# Arduino_sensors.net
KiCad netlist of a schematic drawn in EAGLE
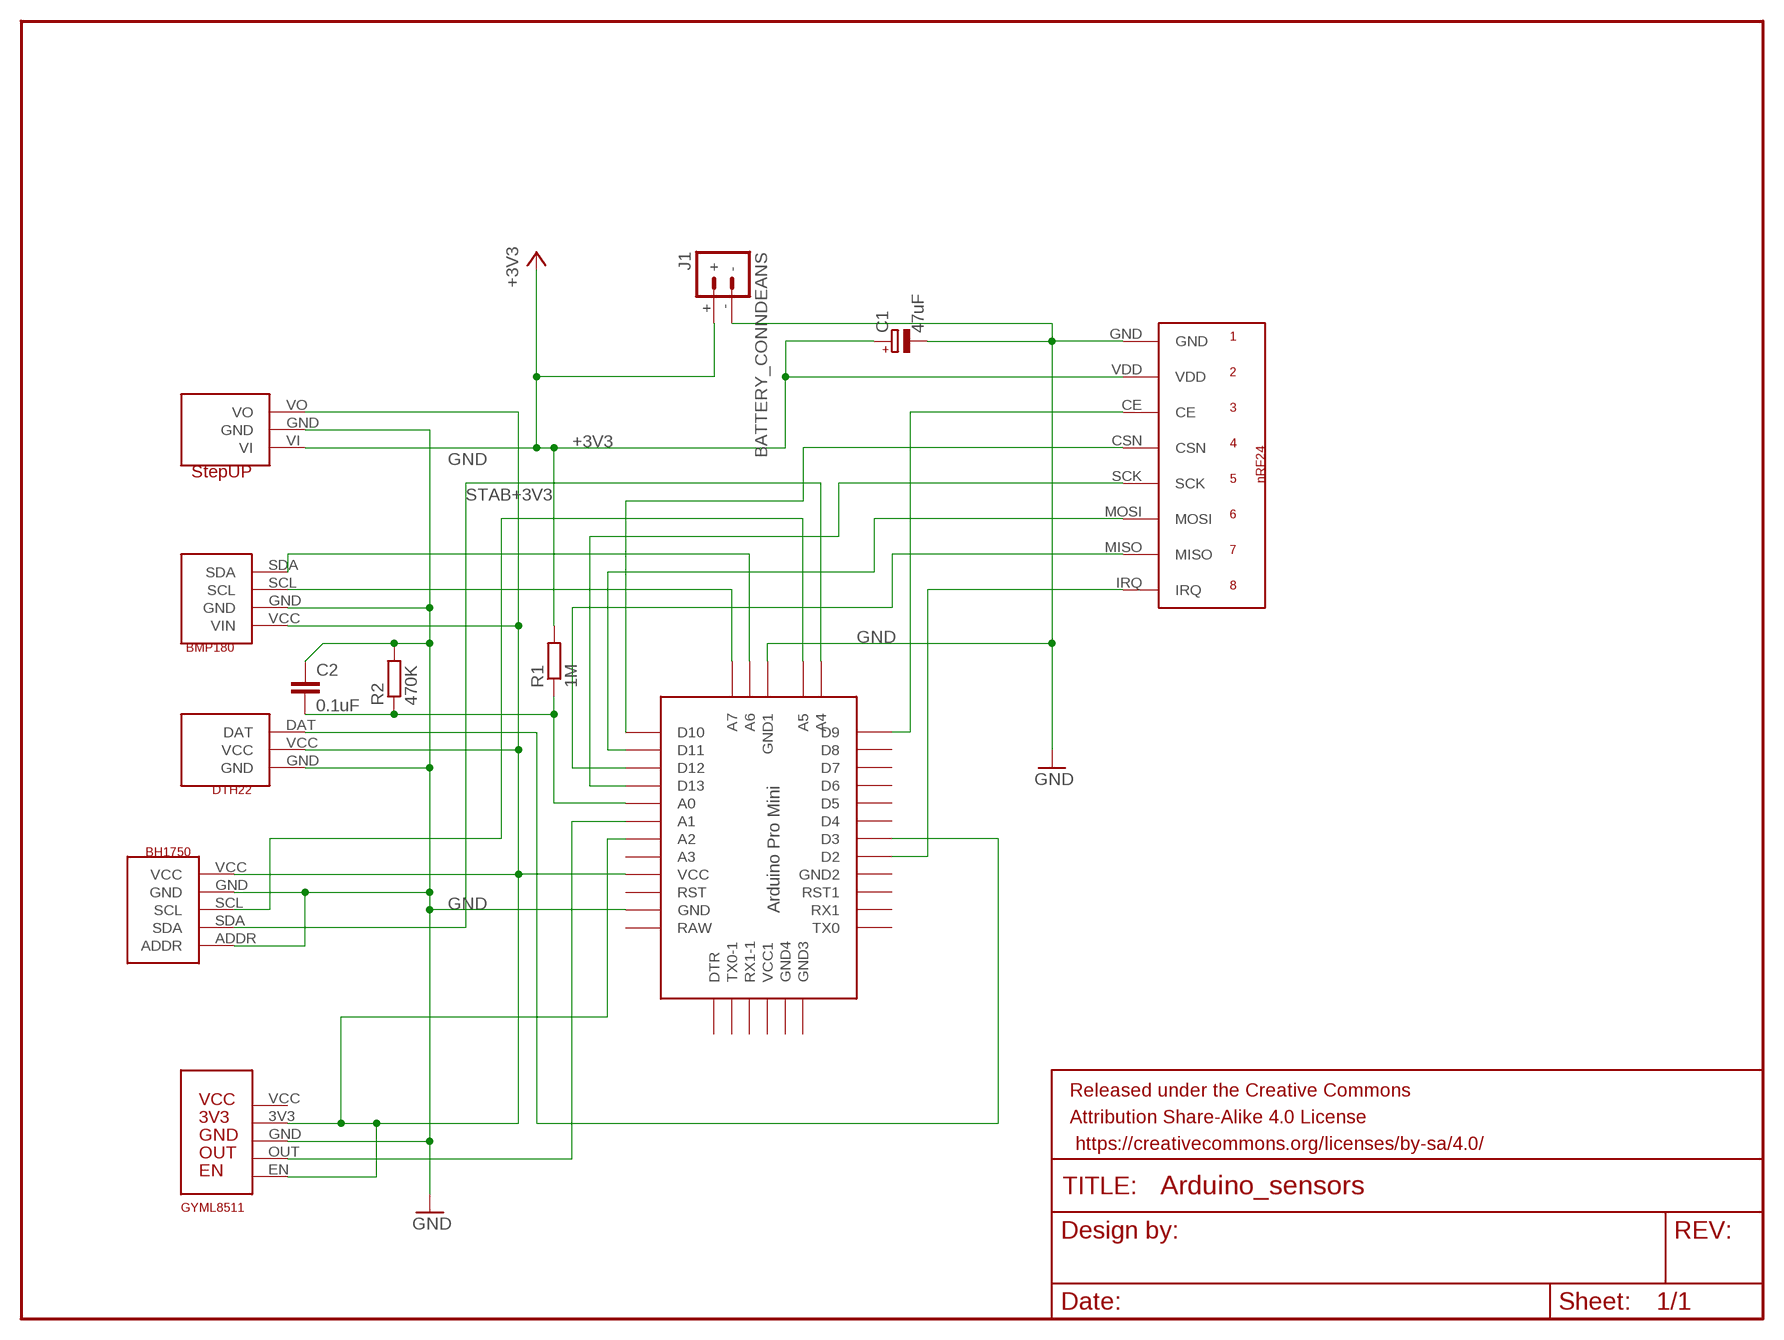
[diagram p0: schematic, sheet 1]

(export (version "E")
  (design (tool "Eeschema 10.0.6"))
  (components
    (comp (ref "ARDUINO_MINI")
      (value "ABK-PRO-MINI")
      (footprint "eagle-import:ABK-PRO-MINI")
      (libsource (lib "eagle-import") (part "ABK-PRO-MINI"))
    )
    (comp (ref "BH1")
      (value "BH1750")
      (footprint "eagle-import:BH1750")
      (libsource (lib "eagle-import") (part "BH1750"))
    )
    (comp (ref "BMP1")
      (value "BMP180")
      (footprint "eagle-import:BMP180")
      (libsource (lib "eagle-import") (part "BMP180"))
    )
    (comp (ref "C1")
      (value "47uF")
      (footprint "eagle-import:E2,5-6")
      (libsource (lib "eagle-import") (part "CPOL-EUE2.5-6"))
    )
    (comp (ref "C2")
      (value "0.1uF")
      (footprint "eagle-import:C025-025X050")
      (libsource (lib "eagle-import") (part "C-EU025-025X050"))
    )
    (comp (ref "DTH1")
      (value "DTH22")
      (footprint "eagle-import:DHT22")
      (libsource (lib "eagle-import") (part "DTH22"))
    )
    (comp (ref "FRAME1")
      (value "FRAME-LETTER")
      (footprint "eagle-import:CREATIVE_COMMONS")
      (libsource (lib "eagle-import") (part "FRAME-LETTER"))
    )
    (comp (ref "J1")
      (value "BATTERY_CONNDEANS")
      (footprint "eagle-import:DEANS")
      (libsource (lib "eagle-import") (part "BATTERY_CONNDEANS"))
    )
    (comp (ref "R1")
      (value "1M")
      (footprint "eagle-import:0207_7")
      (libsource (lib "eagle-import") (part "R-EU_0207/7"))
    )
    (comp (ref "R2")
      (value "470K")
      (footprint "eagle-import:0207_7")
      (libsource (lib "eagle-import") (part "R-EU_0207/7"))
    )
    (comp (ref "STEPUP1")
      (value "STEPUP")
      (footprint "eagle-import:STEPUP")
      (libsource (lib "eagle-import") (part "STEPUP"))
    )
    (comp (ref "U$1")
      (value "GY8511UV_SNR")
      (footprint "eagle-import:GYML8511")
      (libsource (lib "eagle-import") (part "GY8511UV_SNR"))
    )
    (comp (ref "U$2")
      (value "NRF24")
      (footprint "eagle-import:NRF24")
      (libsource (lib "eagle-import") (part "NRF24"))
    )
  )
  (nets
    (net (code "1") (name "+3V3") (class "Default")
      (node (ref "C1") (pin "+") (pinfunction "+_+") (pintype "passive"))
      (node (ref "J1") (pin "+") (pinfunction "+_+") (pintype "passive"))
      (node (ref "R1") (pin "2") (pinfunction "2_2") (pintype "passive"))
      (node (ref "STEPUP1") (pin "VI") (pinfunction "VI_VI") (pintype "bidirectional"))
      (node (ref "U$2") (pin "VDD") (pinfunction "VDD_VDD") (pintype "bidirectional"))
    )
    (net (code "2") (name "/STAB+3V3") (class "Default")
      (node (ref "ARDUINO_MINI") (pin "A2") (pinfunction "A2_A2") (pintype "bidirectional"))
      (node (ref "ARDUINO_MINI") (pin "VCC") (pinfunction "VCC_VCC") (pintype "bidirectional"))
      (node (ref "BH1") (pin "VCC") (pinfunction "VCC_VCC") (pintype "bidirectional"))
      (node (ref "BMP1") (pin "VCC") (pinfunction "VIN_VCC") (pintype "bidirectional"))
      (node (ref "DTH1") (pin "VCC") (pinfunction "VCC_VCC") (pintype "bidirectional"))
      (node (ref "STEPUP1") (pin "VO") (pinfunction "VO_VO") (pintype "bidirectional"))
      (node (ref "U$1") (pin "3V3") (pinfunction "3V3_3V3") (pintype "bidirectional"))
      (node (ref "U$1") (pin "EN") (pinfunction "EN_EN") (pintype "bidirectional"))
    )
    (net (code "3") (name "GND") (class "Default")
      (node (ref "ARDUINO_MINI") (pin "GND") (pinfunction "GND_GND") (pintype "bidirectional"))
      (node (ref "ARDUINO_MINI") (pin "GND4") (pinfunction "GND1_GND4") (pintype "bidirectional"))
      (node (ref "BH1") (pin "ADDR") (pinfunction "ADDR_ADDR") (pintype "bidirectional"))
      (node (ref "BH1") (pin "GND") (pinfunction "GND_GND") (pintype "bidirectional"))
      (node (ref "BMP1") (pin "GND") (pinfunction "GND_GND") (pintype "bidirectional"))
      (node (ref "C1") (pin "-") (pinfunction "-_-") (pintype "passive"))
      (node (ref "C2") (pin "1") (pinfunction "1_1") (pintype "passive"))
      (node (ref "DTH1") (pin "GND") (pinfunction "GND_GND") (pintype "bidirectional"))
      (node (ref "J1") (pin "-") (pinfunction "-_-") (pintype "passive"))
      (node (ref "R2") (pin "2") (pinfunction "2_2") (pintype "passive"))
      (node (ref "STEPUP1") (pin "GND") (pinfunction "GND_GND") (pintype "bidirectional"))
      (node (ref "U$1") (pin "GND") (pinfunction "GND_GND") (pintype "bidirectional"))
      (node (ref "U$2") (pin "GND") (pinfunction "GND_GND") (pintype "bidirectional"))
    )
    (net (code "4") (name "Net-(ARDUINO_MINI-PadA0)") (class "Default")
      (node (ref "ARDUINO_MINI") (pin "A0") (pinfunction "A0_A0") (pintype "bidirectional"))
      (node (ref "C2") (pin "2") (pinfunction "2_2") (pintype "passive"))
      (node (ref "R1") (pin "1") (pinfunction "1_1") (pintype "passive"))
      (node (ref "R2") (pin "1") (pinfunction "1_1") (pintype "passive"))
    )
    (net (code "5") (name "Net-(ARDUINO_MINI-PadA1)") (class "Default")
      (node (ref "ARDUINO_MINI") (pin "A1") (pinfunction "A1_A1") (pintype "bidirectional"))
      (node (ref "U$1") (pin "OUT") (pinfunction "OUT_OUT") (pintype "bidirectional"))
    )
    (net (code "6") (name "Net-(ARDUINO_MINI-PadA4)") (class "Default")
      (node (ref "ARDUINO_MINI") (pin "A4") (pinfunction "A4_A4") (pintype "bidirectional"))
      (node (ref "BH1") (pin "SDA") (pinfunction "SDA_SDA") (pintype "bidirectional"))
    )
    (net (code "7") (name "Net-(ARDUINO_MINI-PadA5)") (class "Default")
      (node (ref "ARDUINO_MINI") (pin "A5") (pinfunction "A5_A5") (pintype "bidirectional"))
      (node (ref "BH1") (pin "SCL") (pinfunction "SCL_SCL") (pintype "bidirectional"))
    )
    (net (code "8") (name "Net-(ARDUINO_MINI-PadA6)") (class "Default")
      (node (ref "ARDUINO_MINI") (pin "A6") (pinfunction "A6_A6") (pintype "bidirectional"))
      (node (ref "BMP1") (pin "SDA") (pinfunction "SDA_SDA") (pintype "bidirectional"))
    )
    (net (code "9") (name "Net-(ARDUINO_MINI-PadA7)") (class "Default")
      (node (ref "ARDUINO_MINI") (pin "A7") (pinfunction "A7_A7") (pintype "bidirectional"))
      (node (ref "BMP1") (pin "SCL") (pinfunction "SCL_SCL") (pintype "bidirectional"))
    )
    (net (code "10") (name "Net-(ARDUINO_MINI-PadD2)") (class "Default")
      (node (ref "ARDUINO_MINI") (pin "D2") (pinfunction "D2_D2") (pintype "bidirectional"))
      (node (ref "U$2") (pin "IRQ") (pinfunction "IRQ_IRQ") (pintype "bidirectional"))
    )
    (net (code "11") (name "Net-(ARDUINO_MINI-PadD3)") (class "Default")
      (node (ref "ARDUINO_MINI") (pin "D3") (pinfunction "D3_D3") (pintype "bidirectional"))
      (node (ref "DTH1") (pin "DAT") (pinfunction "DAT_DAT") (pintype "bidirectional"))
    )
    (net (code "12") (name "Net-(ARDUINO_MINI-PadD9)") (class "Default")
      (node (ref "ARDUINO_MINI") (pin "D9") (pinfunction "D9_D9") (pintype "bidirectional"))
      (node (ref "U$2") (pin "CE") (pinfunction "CE_CE") (pintype "bidirectional"))
    )
    (net (code "13") (name "Net-(ARDUINO_MINI-PadD10)") (class "Default")
      (node (ref "ARDUINO_MINI") (pin "D10") (pinfunction "D10_D10") (pintype "bidirectional"))
      (node (ref "U$2") (pin "CSN") (pinfunction "CSN_CSN") (pintype "bidirectional"))
    )
    (net (code "14") (name "Net-(ARDUINO_MINI-PadD11)") (class "Default")
      (node (ref "ARDUINO_MINI") (pin "D11") (pinfunction "D11_D11") (pintype "bidirectional"))
      (node (ref "U$2") (pin "MOSI") (pinfunction "MOSI_MOSI") (pintype "bidirectional"))
    )
    (net (code "15") (name "Net-(ARDUINO_MINI-PadD12)") (class "Default")
      (node (ref "ARDUINO_MINI") (pin "D12") (pinfunction "D12_D12") (pintype "bidirectional"))
      (node (ref "U$2") (pin "MISO") (pinfunction "MISO_MISO") (pintype "bidirectional"))
    )
    (net (code "16") (name "Net-(ARDUINO_MINI-PadD13)") (class "Default")
      (node (ref "ARDUINO_MINI") (pin "D13") (pinfunction "D13_D13") (pintype "bidirectional"))
      (node (ref "U$2") (pin "SCK") (pinfunction "SCK_SCK") (pintype "bidirectional"))
    )
    (net (code "17") (name "unconnected-(ARDUINO_MINI-GND2-PadGND1)") (class "Default")
      (node (ref "ARDUINO_MINI") (pin "GND1") (pinfunction "GND2_GND1") (pintype "bidirectional"))
    )
    (net (code "18") (name "unconnected-(ARDUINO_MINI-GND3-PadGND2)") (class "Default")
      (node (ref "ARDUINO_MINI") (pin "GND2") (pinfunction "GND3_GND2") (pintype "bidirectional"))
    )
    (net (code "19") (name "unconnected-(ARDUINO_MINI-GND4-PadGND3)") (class "Default")
      (node (ref "ARDUINO_MINI") (pin "GND3") (pinfunction "GND4_GND3") (pintype "bidirectional"))
    )
    (net (code "20") (name "unconnected-(ARDUINO_MINI-PadA3)") (class "Default")
      (node (ref "ARDUINO_MINI") (pin "A3") (pinfunction "A3_A3") (pintype "bidirectional"))
    )
    (net (code "21") (name "unconnected-(ARDUINO_MINI-PadD4)") (class "Default")
      (node (ref "ARDUINO_MINI") (pin "D4") (pinfunction "D4_D4") (pintype "bidirectional"))
    )
    (net (code "22") (name "unconnected-(ARDUINO_MINI-PadD5)") (class "Default")
      (node (ref "ARDUINO_MINI") (pin "D5") (pinfunction "D5_D5") (pintype "bidirectional"))
    )
    (net (code "23") (name "unconnected-(ARDUINO_MINI-PadD6)") (class "Default")
      (node (ref "ARDUINO_MINI") (pin "D6") (pinfunction "D6_D6") (pintype "bidirectional"))
    )
    (net (code "24") (name "unconnected-(ARDUINO_MINI-PadD7)") (class "Default")
      (node (ref "ARDUINO_MINI") (pin "D7") (pinfunction "D7_D7") (pintype "bidirectional"))
    )
    (net (code "25") (name "unconnected-(ARDUINO_MINI-PadD8)") (class "Default")
      (node (ref "ARDUINO_MINI") (pin "D8") (pinfunction "D8_D8") (pintype "bidirectional"))
    )
    (net (code "26") (name "unconnected-(ARDUINO_MINI-PadDTR)") (class "Default")
      (node (ref "ARDUINO_MINI") (pin "DTR") (pinfunction "DTR_DTR") (pintype "bidirectional"))
    )
    (net (code "27") (name "unconnected-(ARDUINO_MINI-PadRAW)") (class "Default")
      (node (ref "ARDUINO_MINI") (pin "RAW") (pinfunction "RAW_RAW") (pintype "bidirectional"))
    )
    (net (code "28") (name "unconnected-(ARDUINO_MINI-PadRST)") (class "Default")
      (node (ref "ARDUINO_MINI") (pin "RST") (pinfunction "RST_RST") (pintype "bidirectional"))
    )
    (net (code "29") (name "unconnected-(ARDUINO_MINI-PadRST1)") (class "Default")
      (node (ref "ARDUINO_MINI") (pin "RST1") (pinfunction "RST1_RST1") (pintype "bidirectional"))
    )
    (net (code "30") (name "unconnected-(ARDUINO_MINI-PadRX1)") (class "Default")
      (node (ref "ARDUINO_MINI") (pin "RX1") (pinfunction "RX1_RX1") (pintype "bidirectional"))
    )
    (net (code "31") (name "unconnected-(ARDUINO_MINI-PadRX1-1)") (class "Default")
      (node (ref "ARDUINO_MINI") (pin "RX1-1") (pinfunction "RX1-1_RX1-1") (pintype "bidirectional"))
    )
    (net (code "32") (name "unconnected-(ARDUINO_MINI-PadTX0)") (class "Default")
      (node (ref "ARDUINO_MINI") (pin "TX0") (pinfunction "TX0_TX0") (pintype "bidirectional"))
    )
    (net (code "33") (name "unconnected-(ARDUINO_MINI-PadTX0-1)") (class "Default")
      (node (ref "ARDUINO_MINI") (pin "TX0-1") (pinfunction "TX0-1_TX0-1") (pintype "bidirectional"))
    )
    (net (code "34") (name "unconnected-(ARDUINO_MINI-PadVCC1)") (class "Default")
      (node (ref "ARDUINO_MINI") (pin "VCC1") (pinfunction "VCC1_VCC1") (pintype "bidirectional"))
    )
    (net (code "35") (name "unconnected-(U$1-PadVCC)") (class "Default")
      (node (ref "U$1") (pin "VCC") (pinfunction "VCC_VCC") (pintype "bidirectional"))
    )
  )
)
